# POWER_BOARD.net
KiCad netlist of a schematic drawn in Altium Designer
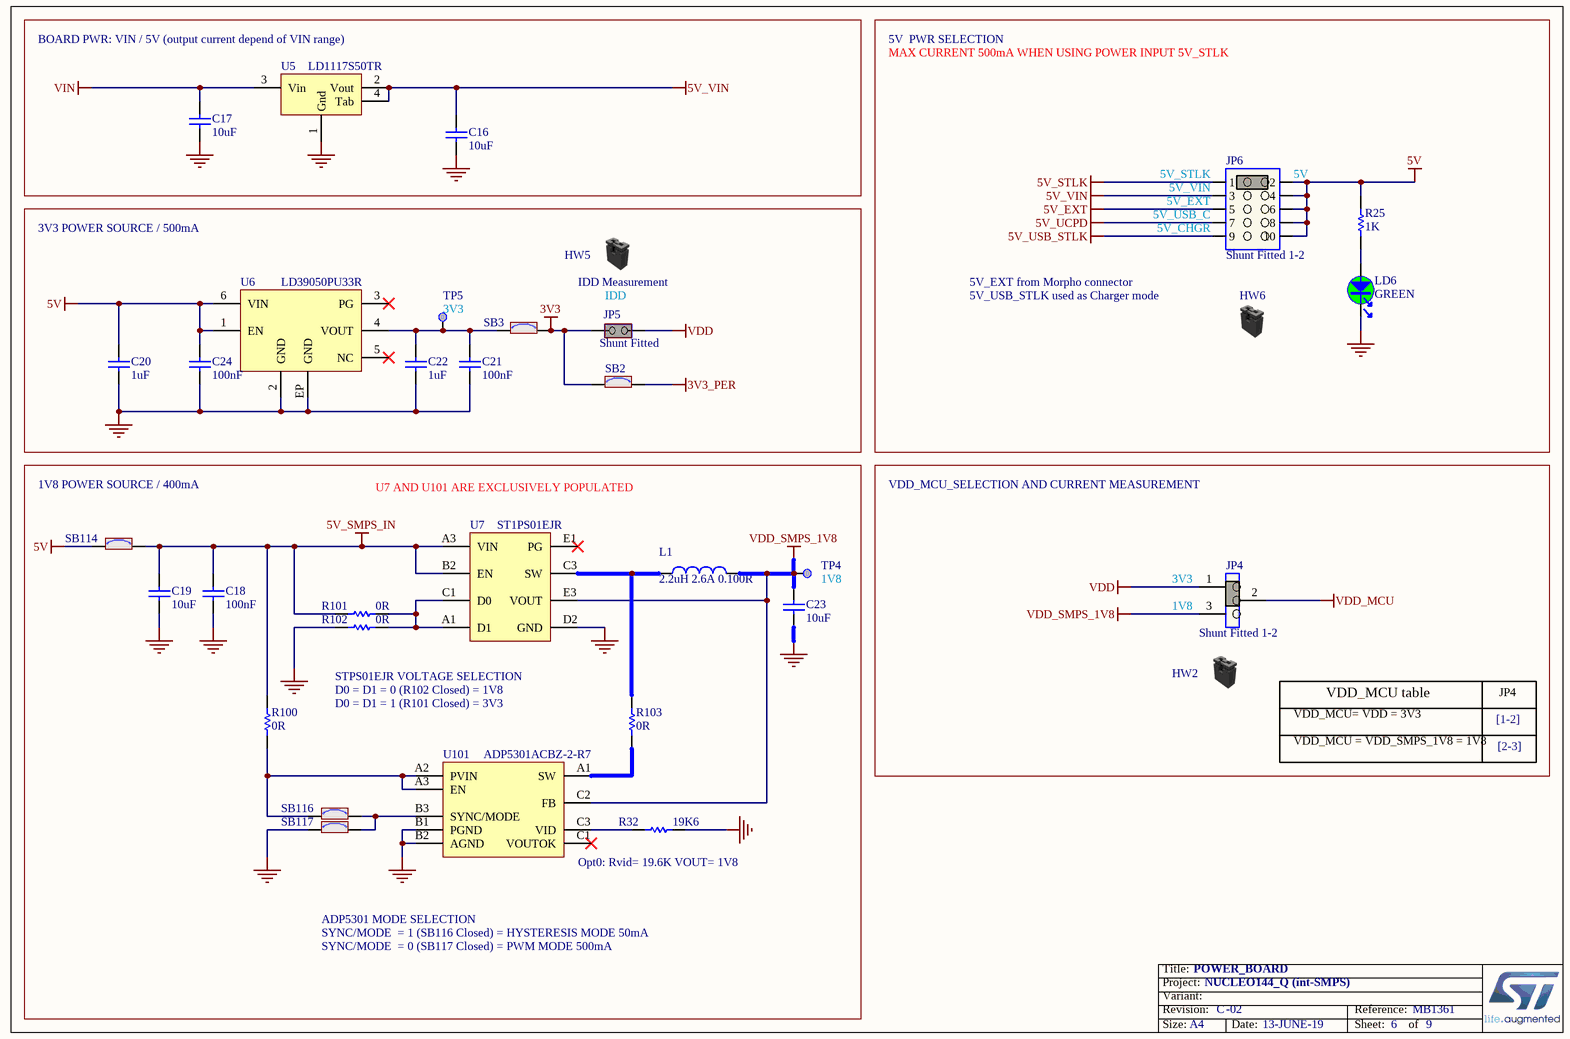
[diagram p0: POWER_BOARD.SchDoc]

(export (version "E")
  (design (tool "Eeschema 10.0.6"))
  (components
    (comp (ref "C16")
      (value "10uF")
      (footprint "C0805")
      (description "Capacitor, MLCC, 10uF, 25V, X5R, 10%, 0805, T=0,85mm")
      (fields
        (field (name "INTERNAL_PART_NUMBER") "MCD-00014")
        (field (name "MANUFACTURER_PART_NUMBER") "CC0805KRX5R8BB106")
        (field (name "PROVIDED_BY") "Subcon")
      )
      (libsource (lib "MCD_PARTS_database") (part "Capacitor"))
    )
    (comp (ref "C17")
      (value "10uF")
      (footprint "C0805")
      (description "Capacitor, MLCC, 10uF, 25V, X5R, 10%, 0805, T=0,85mm")
      (fields
        (field (name "INTERNAL_PART_NUMBER") "MCD-00014")
        (field (name "MANUFACTURER_PART_NUMBER") "CC0805KRX5R8BB106")
        (field (name "PROVIDED_BY") "Subcon")
      )
      (libsource (lib "MCD_PARTS_database") (part "Capacitor"))
    )
    (comp (ref "C18")
      (value "100nF")
      (footprint "C0603")
      (description "Capacitor, MLCC, 100nF, 16V, X7R, 10%, 0603, T=0,8mm")
      (fields
        (field (name "INTERNAL_PART_NUMBER") "MCD-00211")
        (field (name "MANUFACTURER_PART_NUMBER") "CC0603KRX7R7BB104")
        (field (name "PROVIDED_BY") "Subcon")
      )
      (libsource (lib "MCD_PARTS_database") (part "Capacitor"))
    )
    (comp (ref "C19")
      (value "10uF")
      (footprint "C0603")
      (description "Capacitor, MLCC, 10uF, 6V3, X5R, 10%, 0603, T=0,8mm")
      (fields
        (field (name "INTERNAL_PART_NUMBER") "MCD-00243")
        (field (name "MANUFACTURER_PART_NUMBER") "CC0603KRX5R5BB106")
        (field (name "PROVIDED_BY") "Subcon")
      )
      (libsource (lib "MCD_PARTS_database") (part "Capacitor"))
    )
    (comp (ref "C20")
      (value "1uF")
      (footprint "C0603")
      (description "Capacitor, MLCC, 1uF, 16V, X5R, 10%, 0603, T=0,8mm")
      (fields
        (field (name "INTERNAL_PART_NUMBER") "MCD-00010")
        (field (name "MANUFACTURER_PART_NUMBER") "CC0603KRX5R7BB105")
        (field (name "PROVIDED_BY") "SUBCO")
      )
      (libsource (lib "MCD_PARTS_database") (part "Capacitor"))
    )
    (comp (ref "C21")
      (value "100nF")
      (footprint "C0603")
      (description "Capacitor, MLCC, 100nF, 16V, X7R, 10%, 0603, T=0,8mm")
      (fields
        (field (name "INTERNAL_PART_NUMBER") "MCD-00211")
        (field (name "MANUFACTURER_PART_NUMBER") "CC0603KRX7R7BB104")
        (field (name "PROVIDED_BY") "Subcon")
      )
      (libsource (lib "MCD_PARTS_database") (part "Capacitor"))
    )
    (comp (ref "C22")
      (value "1uF")
      (footprint "C0603")
      (description "Capacitor, MLCC, 1uF, 16V, X5R, 10%, 0603, T=0,8mm")
      (fields
        (field (name "INTERNAL_PART_NUMBER") "MCD-00010")
        (field (name "MANUFACTURER_PART_NUMBER") "CC0603KRX5R7BB105")
        (field (name "PROVIDED_BY") "SUBCO")
      )
      (libsource (lib "MCD_PARTS_database") (part "Capacitor"))
    )
    (comp (ref "C23")
      (value "10uF")
      (footprint "C0603")
      (description "Capacitor, MLCC, 10uF, 6V3, X5R, 10%, 0603, T=0,8mm")
      (fields
        (field (name "INTERNAL_PART_NUMBER") "MCD-00243")
        (field (name "MANUFACTURER_PART_NUMBER") "CC0603KRX5R5BB106")
        (field (name "PROVIDED_BY") "Subcon")
      )
      (libsource (lib "MCD_PARTS_database") (part "Capacitor"))
    )
    (comp (ref "C24")
      (value "100nF")
      (footprint "C0603")
      (description "Capacitor, MLCC, 100nF, 16V, X7R, 10%, 0603, T=0,8mm")
      (fields
        (field (name "INTERNAL_PART_NUMBER") "MCD-00211")
        (field (name "MANUFACTURER_PART_NUMBER") "CC0603KRX7R7BB104")
        (field (name "PROVIDED_BY") "Subcon")
      )
      (libsource (lib "MCD_PARTS_database") (part "Capacitor"))
    )
    (comp (ref "HW2")
      (value "~")
      (description "SHUNT 2.54mm BLACK")
      (fields
        (field (name "INTERNAL_PART_NUMBER") "MCD-00043")
        (field (name "MANUFACTURER_PART_NUMBER") "SNT-100-BK-G")
        (field (name "PROVIDED_BY") "Subcon")
      )
      (libsource (lib "MCD_PARTS_database") (part "Shunt Black 2.54mm"))
    )
    (comp (ref "HW5")
      (value "~")
      (description "SHUNT 2.54mm BLACK")
      (fields
        (field (name "INTERNAL_PART_NUMBER") "MCD-00043")
        (field (name "MANUFACTURER_PART_NUMBER") "SNT-100-BK-G")
        (field (name "PROVIDED_BY") "Subcon")
      )
      (libsource (lib "MCD_PARTS_database") (part "Shunt Black 2.54mm"))
    )
    (comp (ref "HW6")
      (value "~")
      (description "SHUNT 2.54mm BLACK")
      (fields
        (field (name "INTERNAL_PART_NUMBER") "MCD-00043")
        (field (name "MANUFACTURER_PART_NUMBER") "SNT-100-BK-G")
        (field (name "PROVIDED_BY") "Subcon")
      )
      (libsource (lib "MCD_PARTS_database") (part "Shunt Black 2.54mm"))
    )
    (comp (ref "JP4")
      (value "Shunt Fitted 1-2")
      (footprint "CON_SAMTEC_TSW-103-07-F-S")
      (description "Header, 3x1, 2,54mm, VR, TH, Height 5.84mm/2.54mm - Shunt Fitted 1-2 by default")
      (fields
        (field (name "INTERNAL_PART_NUMBER") "MCD-00684")
        (field (name "MANUFACTURER_PART_NUMBER") "TSW-103-07-F-S")
        (field (name "PROVIDED_BY") "Subcon")
      )
      (libsource (lib "MCD_PARTS_database") (part "Jumper_Header 3x1 Fitted 1-2"))
    )
    (comp (ref "JP5")
      (value "Shunt Fitted")
      (footprint "CON_SAMTEC_TSW-102-07-G-S")
      (description "Header, 2x1, 2,54mm, VR, TH, Height 5.84mm/2.54mm - Shunt Fitted by default")
      (fields
        (field (name "INTERNAL_PART_NUMBER") "MCD-00683")
        (field (name "MANUFACTURER_PART_NUMBER") "TSW-102-07-x-S")
        (field (name "PROVIDED_BY") "Subcon")
      )
      (libsource (lib "MCD_PARTS_database") (part "Jumper_Header 2x1 Fitted"))
    )
    (comp (ref "JP6")
      (value "Shunt Fitted 1-2")
      (footprint "CON_SAMTEC_TSW-105-07-X-D")
      (description "Header, 5x2, 2,54mm, VR, TH, Height 5.84mm/2.54mm - Shunt Fitted 1-2")
      (fields
        (field (name "INTERNAL_PART_NUMBER") "MCD-01203")
        (field (name "MANUFACTURER_PART_NUMBER") "TSW-105-07-x-D")
        (field (name "PROVIDED_BY") "Subcon")
      )
      (libsource (lib "MCD_PARTS_database") (part "Jumper_Header 5x2 Fitted 1-2"))
    )
    (comp (ref "L1")
      (value "2.2uH 2.6A 0.100R")
      (footprint "IND_TDK_VLS252010HBX-1")
      (description "FIXED IND 2.2UH 2.6A 100 mOHM 20% SMD")
      (fields
        (field (name "INTERNAL_PART_NUMBER") "MCD-00240")
        (field (name "MANUFACTURER_PART_NUMBER") "VLS252010HBX-2R2M-1")
        (field (name "PROVIDED_BY") "Subcon")
      )
      (libsource (lib "MCD_PARTS_database") (part "Inductor"))
    )
    (comp (ref "LD6")
      (value "GREEN")
      (footprint "LED_0603_GREEN")
      (description "LED, Green, 0603")
      (fields
        (field (name "INTERNAL_PART_NUMBER") "MCD-00050")
        (field (name "MANUFACTURER_PART_NUMBER") "19-213SYGC/S530-E2/TR8")
        (field (name "PROVIDED_BY") "Subcon")
      )
      (libsource (lib "MCD_PARTS_database") (part "LED_green"))
    )
    (comp (ref "R25")
      (value "1K")
      (footprint "R0603")
      (description "Resistor,1K,0603,1%,1/10W")
      (fields
        (field (name "INTERNAL_PART_NUMBER") "MCD-00070")
        (field (name "MANUFACTURER_PART_NUMBER") "RC0603FR-071KL")
        (field (name "PROVIDED_BY") "Subcon")
      )
      (libsource (lib "MCD_PARTS_database") (part "Resistor"))
    )
    (comp (ref "R32")
      (value "19K6")
      (footprint "R0603")
      (description "Resistor,19K6,0603,1%,1/10W")
      (fields
        (field (name "INTERNAL_PART_NUMBER") "MCD-00242")
        (field (name "MANUFACTURER_PART_NUMBER") "RC0603FR-0719K6L")
        (field (name "PROVIDED_BY") "Subcon")
      )
      (libsource (lib "MCD_PARTS_database") (part "Resistor"))
    )
    (comp (ref "R100")
      (value "0R")
      (footprint "R0603")
      (description "Resistor,0R,0603,5%,1/10W")
      (fields
        (field (name "INTERNAL_PART_NUMBER") "MCD-00056")
        (field (name "MANUFACTURER_PART_NUMBER") "RC0603JR-070RL")
        (field (name "PROVIDED_BY") "subcon")
      )
      (libsource (lib "MCD_PARTS_database") (part "Resistor"))
    )
    (comp (ref "R101")
      (value "0R")
      (footprint "R0603")
      (description "Resistor,0R,0603,5%,1/10W")
      (fields
        (field (name "INTERNAL_PART_NUMBER") "MCD-00056")
        (field (name "MANUFACTURER_PART_NUMBER") "RC0603JR-070RL")
        (field (name "PROVIDED_BY") "subcon")
      )
      (libsource (lib "MCD_PARTS_database") (part "Resistor"))
    )
    (comp (ref "R102")
      (value "0R")
      (footprint "R0603")
      (description "Resistor,0R,0603,5%,1/10W")
      (fields
        (field (name "INTERNAL_PART_NUMBER") "MCD-00056")
        (field (name "MANUFACTURER_PART_NUMBER") "RC0603JR-070RL")
        (field (name "PROVIDED_BY") "subcon")
      )
      (libsource (lib "MCD_PARTS_database") (part "Resistor"))
    )
    (comp (ref "R103")
      (value "0R")
      (footprint "R0603")
      (description "Resistor,0R,0603,5%,1/10W")
      (fields
        (field (name "INTERNAL_PART_NUMBER") "MCD-00056")
        (field (name "MANUFACTURER_PART_NUMBER") "RC0603JR-070RL")
        (field (name "PROVIDED_BY") "subcon")
      )
      (libsource (lib "MCD_PARTS_database") (part "Resistor"))
    )
    (comp (ref "SB2")
      (value "~")
      (footprint "SOLDER-BRIDGE_R0603-0R")
      (description "Solder Bridge ON")
      (fields (field (name "INTERNAL_PART_NUMBER") "MCD-00071") (field (name "PROVIDED_BY") "Subcon"))
      (libsource (lib "MCD_PARTS_database") (part "SB_ON"))
    )
    (comp (ref "SB3")
      (value "~")
      (footprint "SOLDER-BRIDGE_R0603-0R")
      (description "Solder Bridge ON")
      (fields (field (name "INTERNAL_PART_NUMBER") "MCD-00071") (field (name "PROVIDED_BY") "Subcon"))
      (libsource (lib "MCD_PARTS_database") (part "SB_ON"))
    )
    (comp (ref "SB114")
      (value "~")
      (footprint "SOLDER-BRIDGE_R0603-0R")
      (description "Solder Bridge ON")
      (fields (field (name "INTERNAL_PART_NUMBER") "MCD-00071") (field (name "PROVIDED_BY") "Subcon"))
      (libsource (lib "MCD_PARTS_database") (part "SB_ON"))
    )
    (comp (ref "SB116")
      (value "~")
      (footprint "SOLDER-BRIDGE_R0603-0R")
      (description "Solder Bridge ON")
      (fields (field (name "INTERNAL_PART_NUMBER") "MCD-00071") (field (name "PROVIDED_BY") "Subcon"))
      (libsource (lib "MCD_PARTS_database") (part "SB_ON"))
    )
    (comp (ref "SB117")
      (value "~")
      (footprint "SOLDER-BRIDGE_R0603-0R")
      (description "Solder Bridge ON")
      (fields (field (name "INTERNAL_PART_NUMBER") "MCD-00071") (field (name "PROVIDED_BY") "Subcon"))
      (libsource (lib "MCD_PARTS_database") (part "SB_ON"))
    )
    (comp (ref "TP4")
      (value "~")
      (footprint "TP_SMD_1MM")
      (description "Test Point 1mm")
      (fields
        (field (name "INTERNAL_PART_NUMBER") "MCD-00074")
        (field (name "MANUFACTURER_PART_NUMBER") "n/a")
      )
      (libsource (lib "") (part "Test Point_1"))
    )
    (comp (ref "TP5")
      (value "~")
      (footprint "TP_SMD_1MM")
      (description "Test Point 1mm")
      (fields
        (field (name "INTERNAL_PART_NUMBER") "MCD-00074")
        (field (name "MANUFACTURER_PART_NUMBER") "n/a")
      )
      (libsource (lib "MCD_PARTS_database") (part "Test Point"))
    )
    (comp (ref "U5")
      (value "LD1117S50TR")
      (footprint "REG_SOT223-TAB")
      (description "IC REG LDO 5V 0.8A SOT223")
      (fields
        (field (name "INTERNAL_PART_NUMBER") "MCD-00088")
        (field (name "MANUFACTURER") "STMICROELECTRONICS")
        (field (name "PROVIDED_BY") "Subcon")
      )
      (libsource (lib "MCD_PARTS_database") (part "LD1117S50TR"))
    )
    (comp (ref "U6")
      (value "LD39050PU33R")
      (footprint "ICC_DFN6-EPAD_3X3_P095")
      (description "Low quiescent current and low noise voltage regulators")
      (fields
        (field (name "INTERNAL_PART_NUMBER") "MCD-00215")
        (field (name "MANUFACTURER") "STMICROELECTRONICS")
        (field (name "PROVIDED_BY") "Subcon")
      )
      (libsource (lib "MCD_PARTS_database") (part "LD39050PU33R"))
    )
    (comp (ref "U7")
      (value "ST1PS01EJR")
      (footprint "ICC_FLIP-CHIP-BGA8_1P11X1P41_P040")
      (description "400mA Nano-Quiescent Step down converter")
      (fields
        (field (name "INTERNAL_PART_NUMBER") "MCD-00228")
        (field (name "MANUFACTURER") "STMICROELECTRONICS")
        (field (name "PROVIDED_BY") "Subcon")
      )
      (libsource (lib "MCD_PARTS_database") (part "ST1PS01EJR"))
    )
    (comp (ref "U101")
      (value "ADP5301ACBZ-2-R7")
      (footprint "ICC_WLCSP9_1P65X1P87_P050")
      (description "UL Step down regulator: Opt0")
      (fields
        (field (name "INTERNAL_PART_NUMBER") "MCD-00226")
        (field (name "MANUFACTURER") "ANALOG DEVICES")
        (field (name "PROVIDED_BY") "Subcon")
      )
      (libsource (lib "MCD_PARTS_database") (part "ADP5301"))
    )
  )
  (nets
    (net (code "1") (name "3V3") (class "Default")
      (node (ref "JP5") (pin "1") (pinfunction "COMMON_1") (pintype "passive"))
      (node (ref "SB2") (pin "1") (pinfunction "1_1") (pintype "passive"))
      (node (ref "SB3") (pin "2") (pinfunction "2_2") (pintype "passive"))
    )
    (net (code "2") (name "3V3_PER") (class "Default")
      (node (ref "SB2") (pin "2") (pinfunction "2_2") (pintype "passive"))
    )
    (net (code "3") (name "5V") (class "Default")
      (node (ref "C20") (pin "2") (pinfunction "2_2") (pintype "passive"))
      (node (ref "C24") (pin "2") (pinfunction "2_2") (pintype "passive"))
      (node (ref "JP6") (pin "10") (pinfunction "10_10") (pintype "passive"))
      (node (ref "JP6") (pin "2") (pinfunction "2_2") (pintype "passive"))
      (node (ref "JP6") (pin "4") (pinfunction "4_4") (pintype "passive"))
      (node (ref "JP6") (pin "6") (pinfunction "6_6") (pintype "passive"))
      (node (ref "JP6") (pin "8") (pinfunction "8_8") (pintype "passive"))
      (node (ref "R25") (pin "2") (pinfunction "2_2") (pintype "passive"))
      (node (ref "SB114") (pin "1") (pinfunction "1_1") (pintype "passive"))
      (node (ref "U6") (pin "1") (pinfunction "EN_1") (pintype "passive"))
      (node (ref "U6") (pin "6") (pinfunction "VIN_6") (pintype "passive"))
    )
    (net (code "4") (name "5V_EXT") (class "Default")
      (node (ref "JP6") (pin "5") (pinfunction "5_5") (pintype "passive"))
    )
    (net (code "5") (name "5V_SMPS_IN") (class "Default")
      (node (ref "C18") (pin "2") (pinfunction "2_2") (pintype "passive"))
      (node (ref "C19") (pin "2") (pinfunction "2_2") (pintype "passive"))
      (node (ref "R100") (pin "1") (pinfunction "1_1") (pintype "passive"))
      (node (ref "R101") (pin "2") (pinfunction "2_2") (pintype "passive"))
      (node (ref "SB114") (pin "2") (pinfunction "2_2") (pintype "passive"))
      (node (ref "U7") (pin "A3") (pinfunction "VIN_A3") (pintype "passive"))
      (node (ref "U7") (pin "B2") (pinfunction "EN_B2") (pintype "passive"))
    )
    (net (code "6") (name "5V_STLK") (class "Default")
      (node (ref "JP6") (pin "1") (pinfunction "1_1") (pintype "passive"))
    )
    (net (code "7") (name "5V_UCPD") (class "Default")
      (node (ref "JP6") (pin "7") (pinfunction "7_7") (pintype "passive"))
    )
    (net (code "8") (name "5V_USB_STLK") (class "Default")
      (node (ref "JP6") (pin "9") (pinfunction "9_9") (pintype "passive"))
    )
    (net (code "9") (name "5V_VIN") (class "Default")
      (node (ref "C16") (pin "2") (pinfunction "2_2") (pintype "passive"))
      (node (ref "JP6") (pin "3") (pinfunction "3_3") (pintype "passive"))
      (node (ref "U5") (pin "2") (pinfunction "Vout_2") (pintype "passive"))
      (node (ref "U5") (pin "4") (pinfunction "Tab_4") (pintype "passive"))
    )
    (net (code "10") (name "GND") (class "Default")
      (node (ref "C16") (pin "1") (pinfunction "1_1") (pintype "passive"))
      (node (ref "C17") (pin "1") (pinfunction "1_1") (pintype "passive"))
      (node (ref "C18") (pin "1") (pinfunction "1_1") (pintype "passive"))
      (node (ref "C19") (pin "1") (pinfunction "1_1") (pintype "passive"))
      (node (ref "C20") (pin "1") (pinfunction "1_1") (pintype "passive"))
      (node (ref "C21") (pin "1") (pinfunction "1_1") (pintype "passive"))
      (node (ref "C22") (pin "1") (pinfunction "1_1") (pintype "passive"))
      (node (ref "C23") (pin "1") (pinfunction "1_1") (pintype "passive"))
      (node (ref "C24") (pin "1") (pinfunction "1_1") (pintype "passive"))
      (node (ref "LD6") (pin "2") (pintype "passive"))
      (node (ref "R102") (pin "2") (pinfunction "2_2") (pintype "passive"))
      (node (ref "R32") (pin "2") (pinfunction "2_2") (pintype "passive"))
      (node (ref "SB117") (pin "1") (pinfunction "1_1") (pintype "passive"))
      (node (ref "U101") (pin "B1") (pinfunction "PGND_B1") (pintype "passive"))
      (node (ref "U101") (pin "B2") (pinfunction "AGND_B2") (pintype "passive"))
      (node (ref "U5") (pin "1") (pinfunction "Gnd_1") (pintype "passive"))
      (node (ref "U6") (pin "2") (pinfunction "GND_2") (pintype "passive"))
      (node (ref "U6") (pin "EP") (pinfunction "GND_EP") (pintype "passive"))
      (node (ref "U7") (pin "D2") (pinfunction "GND_D2") (pintype "passive"))
    )
    (net (code "11") (name "Net-(LD6-Pad1)") (class "Default")
      (node (ref "LD6") (pin "1") (pintype "passive"))
      (node (ref "R25") (pin "1") (pinfunction "1_1") (pintype "passive"))
    )
    (net (code "12") (name "Net-(U6-VOUT)") (class "Default")
      (node (ref "C21") (pin "2") (pinfunction "2_2") (pintype "passive"))
      (node (ref "C22") (pin "2") (pinfunction "2_2") (pintype "passive"))
      (node (ref "SB3") (pin "1") (pinfunction "1_1") (pintype "passive"))
      (node (ref "TP5") (pin "1") (pinfunction "1_1") (pintype "passive"))
      (node (ref "U6") (pin "4") (pinfunction "VOUT_4") (pintype "passive"))
    )
    (net (code "13") (name "Net-(U7-D0)") (class "Default")
      (node (ref "R101") (pin "1") (pinfunction "1_1") (pintype "passive"))
      (node (ref "R102") (pin "1") (pinfunction "1_1") (pintype "passive"))
      (node (ref "U7") (pin "A1") (pinfunction "D1_A1") (pintype "passive"))
      (node (ref "U7") (pin "C1") (pinfunction "D0_C1") (pintype "passive"))
    )
    (net (code "14") (name "Net-(U7-SW)") (class "Default")
      (node (ref "L1") (pin "1") (pinfunction "1_1") (pintype "passive"))
      (node (ref "R103") (pin "1") (pinfunction "1_1") (pintype "passive"))
      (node (ref "U7") (pin "C3") (pinfunction "SW_C3") (pintype "passive"))
    )
    (net (code "15") (name "Net-(U101-EN)") (class "Default")
      (node (ref "R100") (pin "2") (pinfunction "2_2") (pintype "passive"))
      (node (ref "SB116") (pin "1") (pinfunction "1_1") (pintype "passive"))
      (node (ref "U101") (pin "A2") (pinfunction "PVIN_A2") (pintype "passive"))
      (node (ref "U101") (pin "A3") (pinfunction "EN_A3") (pintype "passive"))
    )
    (net (code "16") (name "Net-(U101-SW)") (class "Default")
      (node (ref "R103") (pin "2") (pinfunction "2_2") (pintype "passive"))
      (node (ref "U101") (pin "A1") (pinfunction "SW_A1") (pintype "passive"))
    )
    (net (code "17") (name "Net-(U101-SYNC{slash}MODE)") (class "Default")
      (node (ref "SB116") (pin "2") (pinfunction "2_2") (pintype "passive"))
      (node (ref "SB117") (pin "2") (pinfunction "2_2") (pintype "passive"))
      (node (ref "U101") (pin "B3") (pinfunction "SYNC/MODE_B3") (pintype "passive"))
    )
    (net (code "18") (name "Net-(U101-VID)") (class "Default")
      (node (ref "R32") (pin "1") (pinfunction "1_1") (pintype "passive"))
      (node (ref "U101") (pin "C3") (pinfunction "VID_C3") (pintype "passive"))
    )
    (net (code "19") (name "VDD") (class "Default")
      (node (ref "JP4") (pin "1") (pinfunction "1_1") (pintype "passive"))
      (node (ref "JP5") (pin "2") (pinfunction "NO_2") (pintype "passive"))
    )
    (net (code "20") (name "VDD_MCU") (class "Default")
      (node (ref "JP4") (pin "2") (pinfunction "2_2") (pintype "passive"))
    )
    (net (code "21") (name "VDD_SMPS_1V8") (class "Default")
      (node (ref "C23") (pin "2") (pinfunction "2_2") (pintype "passive"))
      (node (ref "JP4") (pin "3") (pinfunction "3_3") (pintype "passive"))
      (node (ref "L1") (pin "2") (pinfunction "2_2") (pintype "passive"))
      (node (ref "TP4") (pin "1") (pinfunction "1_1") (pintype "passive"))
      (node (ref "U101") (pin "C2") (pinfunction "FB_C2") (pintype "passive"))
      (node (ref "U7") (pin "E3") (pinfunction "VOUT_E3") (pintype "passive"))
    )
    (net (code "22") (name "VIN") (class "Default")
      (node (ref "C17") (pin "2") (pinfunction "2_2") (pintype "passive"))
      (node (ref "U5") (pin "3") (pinfunction "Vin_3") (pintype "passive"))
    )
    (net (code "23") (name "unconnected-(U6-NC-Pad5)") (class "Default")
      (node (ref "U6") (pin "5") (pinfunction "NC_5") (pintype "passive+no_connect"))
    )
    (net (code "24") (name "unconnected-(U6-PG-Pad3)") (class "Default")
      (node (ref "U6") (pin "3") (pinfunction "PG_3") (pintype "passive+no_connect"))
    )
    (net (code "25") (name "unconnected-(U7-PG-PadE1)") (class "Default")
      (node (ref "U7") (pin "E1") (pinfunction "PG_E1") (pintype "passive+no_connect"))
    )
    (net (code "26") (name "unconnected-(U101-VOUTOK-PadC1)") (class "Default")
      (node (ref "U101") (pin "C1") (pinfunction "VOUTOK_C1") (pintype "passive+no_connect"))
    )
  )
)
